# LM2596ADJ.net
KiCad netlist of a schematic drawn in EAGLE
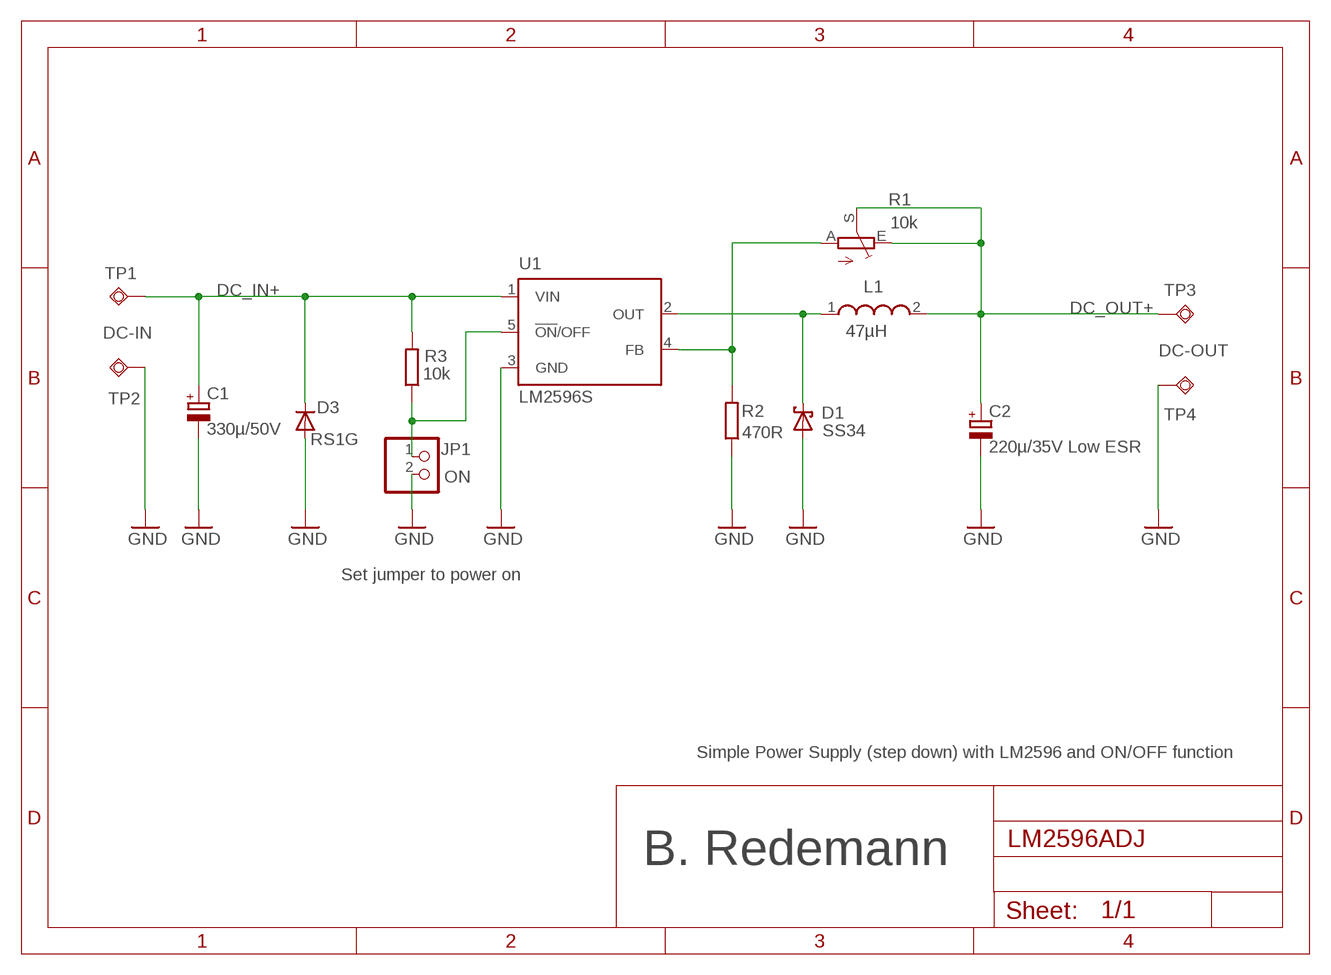
[diagram p0: schematic, sheet 1]

(export (version "E")
  (design (tool "Eeschema 10.0.6"))
  (components
    (comp (ref "C1")
      (value "330µ/50V")
      (footprint "eagle-import:PANASONIC_G")
      (fields (field (name "MF") "Panasonic"))
      (libsource (lib "eagle-import") (part "CPOL-EUG"))
    )
    (comp (ref "C2")
      (value "220µ/35V Low ESR")
      (footprint "eagle-import:PANASONIC_F")
      (fields (field (name "MF") "Panasonic"))
      (libsource (lib "eagle-import") (part "CPOL-EUF"))
    )
    (comp (ref "D1")
      (value "SS34")
      (footprint "eagle-import:SMB")
      (libsource (lib "eagle-import") (part "SCHOTTKY-DIODESMD"))
    )
    (comp (ref "D3")
      (value "RS1G")
      (footprint "eagle-import:DO214AC")
      (fields (field (name "MF") "multicomp"))
      (libsource (lib "eagle-import") (part "DIODE-DO214AC"))
    )
    (comp (ref "JP1")
      (value "ON")
      (footprint "eagle-import:1X02")
      (libsource (lib "eagle-import") (part "PINHD-1X2"))
    )
    (comp (ref "L1")
      (value "47µH")
      (footprint "eagle-import:WE-PD_1260_1245_1280_1210")
      (fields (field (name "MF") "Wuerth"))
      (libsource (lib "eagle-import") (part "WE-PD_1260/1245/1280/1210"))
    )
    (comp (ref "R1")
      (value "10k")
      (footprint "eagle-import:RJ9W")
      (libsource (lib "eagle-import") (part "TRIM_EU-RJ9W"))
    )
    (comp (ref "R2")
      (value "470R")
      (footprint "eagle-import:M0805")
      (libsource (lib "eagle-import") (part "R-EU_M0805"))
    )
    (comp (ref "R3")
      (value "10k")
      (footprint "eagle-import:M0805")
      (libsource (lib "eagle-import") (part "R-EU_M0805"))
    )
    (comp (ref "TP1")
      (value "DC_IN")
      (footprint "eagle-import:P1-13Y")
      (libsource (lib "eagle-import") (part "TPSQPAD1-13Y"))
    )
    (comp (ref "TP2")
      (value "GND")
      (footprint "eagle-import:P1-13Y")
      (libsource (lib "eagle-import") (part "TPSQPAD1-13Y"))
    )
    (comp (ref "TP3")
      (value "DC_OUT")
      (footprint "eagle-import:P1-13Y")
      (libsource (lib "eagle-import") (part "TPSQPAD1-13Y"))
    )
    (comp (ref "TP4")
      (value "GND")
      (footprint "eagle-import:P1-13Y")
      (libsource (lib "eagle-import") (part "TPSQPAD1-13Y"))
    )
    (comp (ref "U1")
      (value "LM2596S")
      (footprint "eagle-import:TO263-5")
      (fields (field (name "MF") "NATIONAL SEMICONDUCTOR") (field (name "MPN") "LM2596S-ADJ/NOPB"))
      (libsource (lib "eagle-import") (part "LM2596S"))
    )
  )
  (nets
    (net (code "1") (name "/DC_IN+") (class "Default")
      (node (ref "C1") (pin "+") (pinfunction "+_+") (pintype "passive"))
      (node (ref "D3") (pin "C") (pinfunction "C_C") (pintype "passive"))
      (node (ref "R3") (pin "2") (pinfunction "2_2") (pintype "passive"))
      (node (ref "TP1") (pin "TP") (pinfunction "TP_TP") (pintype "input"))
      (node (ref "U1") (pin "1") (pinfunction "VIN_1") (pintype "input"))
    )
    (net (code "2") (name "/DC_OUT+") (class "Default")
      (node (ref "C2") (pin "+") (pinfunction "+_+") (pintype "passive"))
      (node (ref "L1") (pin "2") (pinfunction "2_2") (pintype "passive"))
      (node (ref "R1") (pin "E") (pinfunction "E_E") (pintype "passive"))
      (node (ref "R1") (pin "S") (pinfunction "S_S") (pintype "passive"))
      (node (ref "TP3") (pin "TP") (pinfunction "TP_TP") (pintype "input"))
    )
    (net (code "3") (name "GND") (class "Default")
      (node (ref "C1") (pin "-") (pinfunction "-_-") (pintype "passive"))
      (node (ref "C2") (pin "-") (pinfunction "-_-") (pintype "passive"))
      (node (ref "D1") (pin "A") (pinfunction "A_A") (pintype "passive"))
      (node (ref "D3") (pin "A") (pinfunction "A_A") (pintype "passive"))
      (node (ref "JP1") (pin "2") (pinfunction "2_2") (pintype "passive"))
      (node (ref "R2") (pin "1") (pinfunction "1_1") (pintype "passive"))
      (node (ref "TP2") (pin "TP") (pinfunction "TP_TP") (pintype "input"))
      (node (ref "TP4") (pin "TP") (pinfunction "TP_TP") (pintype "input"))
      (node (ref "U1") (pin "3") (pinfunction "GND_3") (pintype "power_in"))
    )
    (net (code "4") (name "Net-(U1-FB)") (class "Default")
      (node (ref "R1") (pin "A") (pinfunction "A_A") (pintype "passive"))
      (node (ref "R2") (pin "2") (pinfunction "2_2") (pintype "passive"))
      (node (ref "U1") (pin "4") (pinfunction "FB_4") (pintype "input"))
    )
    (net (code "5") (name "Net-(U1-OUT)") (class "Default")
      (node (ref "D1") (pin "C") (pinfunction "C_C") (pintype "passive"))
      (node (ref "L1") (pin "1") (pinfunction "1_1") (pintype "passive"))
      (node (ref "U1") (pin "2") (pinfunction "OUT_2") (pintype "output"))
    )
    (net (code "6") (name "Net-(U1-~{ON}{slash}OFF)") (class "Default")
      (node (ref "JP1") (pin "1") (pinfunction "1_1") (pintype "passive"))
      (node (ref "R3") (pin "1") (pinfunction "1_1") (pintype "passive"))
      (node (ref "U1") (pin "5") (pinfunction "~{ON}/OFF_5") (pintype "input"))
    )
  )
)
